# Mosaic-Support.net
KiCad netlist of a schematic drawn in Altium Designer
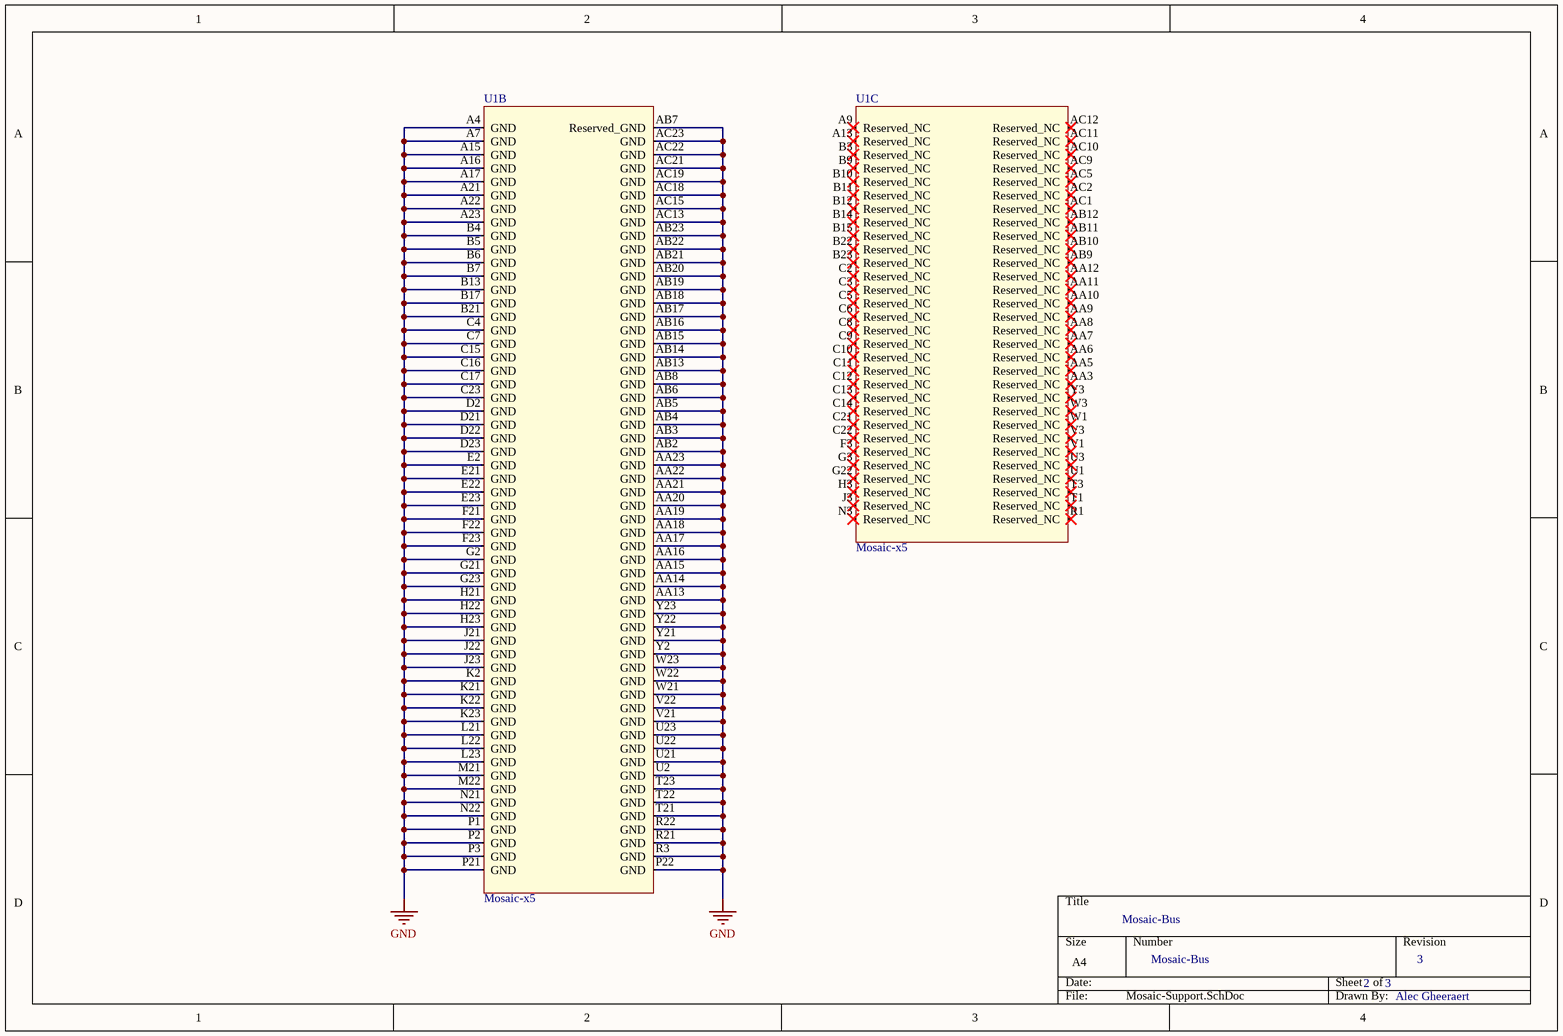
[diagram p0: Mosaic-Support.SchDoc]

(export (version "E")
  (design (tool "Eeschema 10.0.6"))
  (components
    (comp (ref "U1")
      (value "Mosaic-x5")
      (footprint "Mosaic-x5")
      (description "Septentrio Mosaic x5")
      (libsource (lib "Ghrt") (part "Mosaic-x5"))
    )
  )
  (nets
    (net (code "1") (name "GND") (class "Default")
      (node (ref "U1") (pin "A15") (pinfunction "GND_A15") (pintype "power_in"))
      (node (ref "U1") (pin "A16") (pinfunction "GND_A16") (pintype "power_in"))
      (node (ref "U1") (pin "A17") (pinfunction "GND_A17") (pintype "power_in"))
      (node (ref "U1") (pin "A21") (pinfunction "GND_A21") (pintype "power_in"))
      (node (ref "U1") (pin "A22") (pinfunction "GND_A22") (pintype "power_in"))
      (node (ref "U1") (pin "A23") (pinfunction "GND_A23") (pintype "power_in"))
      (node (ref "U1") (pin "A4") (pinfunction "GND_A4") (pintype "power_in"))
      (node (ref "U1") (pin "A7") (pinfunction "GND_A7") (pintype "power_in"))
      (node (ref "U1") (pin "AA13") (pinfunction "GND_AA13") (pintype "power_in"))
      (node (ref "U1") (pin "AA14") (pinfunction "GND_AA14") (pintype "power_in"))
      (node (ref "U1") (pin "AA15") (pinfunction "GND_AA15") (pintype "power_in"))
      (node (ref "U1") (pin "AA16") (pinfunction "GND_AA16") (pintype "power_in"))
      (node (ref "U1") (pin "AA17") (pinfunction "GND_AA17") (pintype "power_in"))
      (node (ref "U1") (pin "AA18") (pinfunction "GND_AA18") (pintype "power_in"))
      (node (ref "U1") (pin "AA19") (pinfunction "GND_AA19") (pintype "power_in"))
      (node (ref "U1") (pin "AA20") (pinfunction "GND_AA20") (pintype "power_in"))
      (node (ref "U1") (pin "AA21") (pinfunction "GND_AA21") (pintype "power_in"))
      (node (ref "U1") (pin "AA22") (pinfunction "GND_AA22") (pintype "power_in"))
      (node (ref "U1") (pin "AA23") (pinfunction "GND_AA23") (pintype "power_in"))
      (node (ref "U1") (pin "AB13") (pinfunction "GND_AB13") (pintype "power_in"))
      (node (ref "U1") (pin "AB14") (pinfunction "GND_AB14") (pintype "power_in"))
      (node (ref "U1") (pin "AB15") (pinfunction "GND_AB15") (pintype "power_in"))
      (node (ref "U1") (pin "AB16") (pinfunction "GND_AB16") (pintype "power_in"))
      (node (ref "U1") (pin "AB17") (pinfunction "GND_AB17") (pintype "power_in"))
      (node (ref "U1") (pin "AB18") (pinfunction "GND_AB18") (pintype "power_in"))
      (node (ref "U1") (pin "AB19") (pinfunction "GND_AB19") (pintype "power_in"))
      (node (ref "U1") (pin "AB2") (pinfunction "GND_AB2") (pintype "power_in"))
      (node (ref "U1") (pin "AB20") (pinfunction "GND_AB20") (pintype "power_in"))
      (node (ref "U1") (pin "AB21") (pinfunction "GND_AB21") (pintype "power_in"))
      (node (ref "U1") (pin "AB22") (pinfunction "GND_AB22") (pintype "power_in"))
      (node (ref "U1") (pin "AB23") (pinfunction "GND_AB23") (pintype "power_in"))
      (node (ref "U1") (pin "AB3") (pinfunction "GND_AB3") (pintype "power_in"))
      (node (ref "U1") (pin "AB4") (pinfunction "GND_AB4") (pintype "power_in"))
      (node (ref "U1") (pin "AB5") (pinfunction "GND_AB5") (pintype "power_in"))
      (node (ref "U1") (pin "AB6") (pinfunction "GND_AB6") (pintype "power_in"))
      (node (ref "U1") (pin "AB7") (pinfunction "Reserved_GND_AB7") (pintype "power_in"))
      (node (ref "U1") (pin "AB8") (pinfunction "GND_AB8") (pintype "power_in"))
      (node (ref "U1") (pin "AC13") (pinfunction "GND_AC13") (pintype "power_in"))
      (node (ref "U1") (pin "AC15") (pinfunction "GND_AC15") (pintype "power_in"))
      (node (ref "U1") (pin "AC18") (pinfunction "GND_AC18") (pintype "power_in"))
      (node (ref "U1") (pin "AC19") (pinfunction "GND_AC19") (pintype "power_in"))
      (node (ref "U1") (pin "AC21") (pinfunction "GND_AC21") (pintype "power_in"))
      (node (ref "U1") (pin "AC22") (pinfunction "GND_AC22") (pintype "power_in"))
      (node (ref "U1") (pin "AC23") (pinfunction "GND_AC23") (pintype "power_in"))
      (node (ref "U1") (pin "B13") (pinfunction "GND_B13") (pintype "power_in"))
      (node (ref "U1") (pin "B17") (pinfunction "GND_B17") (pintype "power_in"))
      (node (ref "U1") (pin "B21") (pinfunction "GND_B21") (pintype "power_in"))
      (node (ref "U1") (pin "B4") (pinfunction "GND_B4") (pintype "power_in"))
      (node (ref "U1") (pin "B5") (pinfunction "GND_B5") (pintype "power_in"))
      (node (ref "U1") (pin "B6") (pinfunction "GND_B6") (pintype "power_in"))
      (node (ref "U1") (pin "B7") (pinfunction "GND_B7") (pintype "power_in"))
      (node (ref "U1") (pin "C15") (pinfunction "GND_C15") (pintype "power_in"))
      (node (ref "U1") (pin "C16") (pinfunction "GND_C16") (pintype "power_in"))
      (node (ref "U1") (pin "C17") (pinfunction "GND_C17") (pintype "power_in"))
      (node (ref "U1") (pin "C23") (pinfunction "GND_C23") (pintype "power_in"))
      (node (ref "U1") (pin "C4") (pinfunction "GND_C4") (pintype "power_in"))
      (node (ref "U1") (pin "C7") (pinfunction "GND_C7") (pintype "power_in"))
      (node (ref "U1") (pin "D2") (pinfunction "GND_D2") (pintype "power_in"))
      (node (ref "U1") (pin "D21") (pinfunction "GND_D21") (pintype "power_in"))
      (node (ref "U1") (pin "D22") (pinfunction "GND_D22") (pintype "power_in"))
      (node (ref "U1") (pin "D23") (pinfunction "GND_D23") (pintype "power_in"))
      (node (ref "U1") (pin "E2") (pinfunction "GND_E2") (pintype "power_in"))
      (node (ref "U1") (pin "E21") (pinfunction "GND_E21") (pintype "power_in"))
      (node (ref "U1") (pin "E22") (pinfunction "GND_E22") (pintype "power_in"))
      (node (ref "U1") (pin "E23") (pinfunction "GND_E23") (pintype "power_in"))
      (node (ref "U1") (pin "F21") (pinfunction "GND_F21") (pintype "power_in"))
      (node (ref "U1") (pin "F22") (pinfunction "GND_F22") (pintype "power_in"))
      (node (ref "U1") (pin "F23") (pinfunction "GND_F23") (pintype "power_in"))
      (node (ref "U1") (pin "G2") (pinfunction "GND_G2") (pintype "power_in"))
      (node (ref "U1") (pin "G21") (pinfunction "GND_G21") (pintype "power_in"))
      (node (ref "U1") (pin "G23") (pinfunction "GND_G23") (pintype "power_in"))
      (node (ref "U1") (pin "H21") (pinfunction "GND_H21") (pintype "power_in"))
      (node (ref "U1") (pin "H22") (pinfunction "GND_H22") (pintype "power_in"))
      (node (ref "U1") (pin "H23") (pinfunction "GND_H23") (pintype "power_in"))
      (node (ref "U1") (pin "J21") (pinfunction "GND_J21") (pintype "power_in"))
      (node (ref "U1") (pin "J22") (pinfunction "GND_J22") (pintype "power_in"))
      (node (ref "U1") (pin "J23") (pinfunction "GND_J23") (pintype "power_in"))
      (node (ref "U1") (pin "K2") (pinfunction "GND_K2") (pintype "power_in"))
      (node (ref "U1") (pin "K21") (pinfunction "GND_K21") (pintype "power_in"))
      (node (ref "U1") (pin "K22") (pinfunction "GND_K22") (pintype "power_in"))
      (node (ref "U1") (pin "K23") (pinfunction "GND_K23") (pintype "power_in"))
      (node (ref "U1") (pin "L21") (pinfunction "GND_L21") (pintype "power_in"))
      (node (ref "U1") (pin "L22") (pinfunction "GND_L22") (pintype "power_in"))
      (node (ref "U1") (pin "L23") (pinfunction "GND_L23") (pintype "power_in"))
      (node (ref "U1") (pin "M21") (pinfunction "GND_M21") (pintype "power_in"))
      (node (ref "U1") (pin "M22") (pinfunction "GND_M22") (pintype "power_in"))
      (node (ref "U1") (pin "N21") (pinfunction "GND_N21") (pintype "power_in"))
      (node (ref "U1") (pin "N22") (pinfunction "GND_N22") (pintype "power_in"))
      (node (ref "U1") (pin "P1") (pinfunction "GND_P1") (pintype "power_in"))
      (node (ref "U1") (pin "P2") (pinfunction "GND_P2") (pintype "power_in"))
      (node (ref "U1") (pin "P21") (pinfunction "GND_P21") (pintype "power_in"))
      (node (ref "U1") (pin "P22") (pinfunction "GND_P22") (pintype "power_in"))
      (node (ref "U1") (pin "P3") (pinfunction "GND_P3") (pintype "power_in"))
      (node (ref "U1") (pin "R21") (pinfunction "GND_R21") (pintype "power_in"))
      (node (ref "U1") (pin "R22") (pinfunction "GND_R22") (pintype "power_in"))
      (node (ref "U1") (pin "R3") (pinfunction "GND_R3") (pintype "power_in"))
      (node (ref "U1") (pin "T21") (pinfunction "GND_T21") (pintype "power_in"))
      (node (ref "U1") (pin "T22") (pinfunction "GND_T22") (pintype "power_in"))
      (node (ref "U1") (pin "T23") (pinfunction "GND_T23") (pintype "power_in"))
      (node (ref "U1") (pin "U2") (pinfunction "GND_U2") (pintype "power_in"))
      (node (ref "U1") (pin "U21") (pinfunction "GND_U21") (pintype "power_in"))
      (node (ref "U1") (pin "U22") (pinfunction "GND_U22") (pintype "power_in"))
      (node (ref "U1") (pin "U23") (pinfunction "GND_U23") (pintype "power_in"))
      (node (ref "U1") (pin "V21") (pinfunction "GND_V21") (pintype "power_in"))
      (node (ref "U1") (pin "V22") (pinfunction "GND_V22") (pintype "power_in"))
      (node (ref "U1") (pin "W21") (pinfunction "GND_W21") (pintype "power_in"))
      (node (ref "U1") (pin "W22") (pinfunction "GND_W22") (pintype "power_in"))
      (node (ref "U1") (pin "W23") (pinfunction "GND_W23") (pintype "power_in"))
      (node (ref "U1") (pin "Y2") (pinfunction "GND_Y2") (pintype "power_in"))
      (node (ref "U1") (pin "Y21") (pinfunction "GND_Y21") (pintype "power_in"))
      (node (ref "U1") (pin "Y22") (pinfunction "GND_Y22") (pintype "power_in"))
      (node (ref "U1") (pin "Y23") (pinfunction "GND_Y23") (pintype "power_in"))
    )
    (net (code "2") (name "unconnected-(U1C-Reserved_NC-PadA9)") (class "Default")
      (node (ref "U1") (pin "A9") (pinfunction "Reserved_NC_A9") (pintype "passive+no_connect"))
    )
    (net (code "3") (name "unconnected-(U1C-Reserved_NC-PadA13)") (class "Default")
      (node (ref "U1") (pin "A13") (pinfunction "Reserved_NC_A13") (pintype "passive+no_connect"))
    )
    (net (code "4") (name "unconnected-(U1C-Reserved_NC-PadAA3)") (class "Default")
      (node (ref "U1") (pin "AA3") (pinfunction "Reserved_NC_AA3") (pintype "passive+no_connect"))
    )
    (net (code "5") (name "unconnected-(U1C-Reserved_NC-PadAA5)") (class "Default")
      (node (ref "U1") (pin "AA5") (pinfunction "Reserved_NC_AA5") (pintype "passive+no_connect"))
    )
    (net (code "6") (name "unconnected-(U1C-Reserved_NC-PadAA6)") (class "Default")
      (node (ref "U1") (pin "AA6") (pinfunction "Reserved_NC_AA6") (pintype "passive+no_connect"))
    )
    (net (code "7") (name "unconnected-(U1C-Reserved_NC-PadAA7)") (class "Default")
      (node (ref "U1") (pin "AA7") (pinfunction "Reserved_NC_AA7") (pintype "passive+no_connect"))
    )
    (net (code "8") (name "unconnected-(U1C-Reserved_NC-PadAA8)") (class "Default")
      (node (ref "U1") (pin "AA8") (pinfunction "Reserved_NC_AA8") (pintype "passive+no_connect"))
    )
    (net (code "9") (name "unconnected-(U1C-Reserved_NC-PadAA9)") (class "Default")
      (node (ref "U1") (pin "AA9") (pinfunction "Reserved_NC_AA9") (pintype "passive+no_connect"))
    )
    (net (code "10") (name "unconnected-(U1C-Reserved_NC-PadAA10)") (class "Default")
      (node (ref "U1") (pin "AA10") (pinfunction "Reserved_NC_AA10") (pintype "passive+no_connect"))
    )
    (net (code "11") (name "unconnected-(U1C-Reserved_NC-PadAA11)") (class "Default")
      (node (ref "U1") (pin "AA11") (pinfunction "Reserved_NC_AA11") (pintype "passive+no_connect"))
    )
    (net (code "12") (name "unconnected-(U1C-Reserved_NC-PadAA12)") (class "Default")
      (node (ref "U1") (pin "AA12") (pinfunction "Reserved_NC_AA12") (pintype "passive+no_connect"))
    )
    (net (code "13") (name "unconnected-(U1C-Reserved_NC-PadAB9)") (class "Default")
      (node (ref "U1") (pin "AB9") (pinfunction "Reserved_NC_AB9") (pintype "passive+no_connect"))
    )
    (net (code "14") (name "unconnected-(U1C-Reserved_NC-PadAB10)") (class "Default")
      (node (ref "U1") (pin "AB10") (pinfunction "Reserved_NC_AB10") (pintype "passive+no_connect"))
    )
    (net (code "15") (name "unconnected-(U1C-Reserved_NC-PadAB11)") (class "Default")
      (node (ref "U1") (pin "AB11") (pinfunction "Reserved_NC_AB11") (pintype "passive+no_connect"))
    )
    (net (code "16") (name "unconnected-(U1C-Reserved_NC-PadAB12)") (class "Default")
      (node (ref "U1") (pin "AB12") (pinfunction "Reserved_NC_AB12") (pintype "passive+no_connect"))
    )
    (net (code "17") (name "unconnected-(U1C-Reserved_NC-PadAC1)") (class "Default")
      (node (ref "U1") (pin "AC1") (pinfunction "Reserved_NC_AC1") (pintype "passive+no_connect"))
    )
    (net (code "18") (name "unconnected-(U1C-Reserved_NC-PadAC2)") (class "Default")
      (node (ref "U1") (pin "AC2") (pinfunction "Reserved_NC_AC2") (pintype "passive+no_connect"))
    )
    (net (code "19") (name "unconnected-(U1C-Reserved_NC-PadAC5)") (class "Default")
      (node (ref "U1") (pin "AC5") (pinfunction "Reserved_NC_AC5") (pintype "passive+no_connect"))
    )
    (net (code "20") (name "unconnected-(U1C-Reserved_NC-PadAC9)") (class "Default")
      (node (ref "U1") (pin "AC9") (pinfunction "Reserved_NC_AC9") (pintype "passive+no_connect"))
    )
    (net (code "21") (name "unconnected-(U1C-Reserved_NC-PadAC10)") (class "Default")
      (node (ref "U1") (pin "AC10") (pinfunction "Reserved_NC_AC10") (pintype "passive+no_connect"))
    )
    (net (code "22") (name "unconnected-(U1C-Reserved_NC-PadAC11)") (class "Default")
      (node (ref "U1") (pin "AC11") (pinfunction "Reserved_NC_AC11") (pintype "passive+no_connect"))
    )
    (net (code "23") (name "unconnected-(U1C-Reserved_NC-PadAC12)") (class "Default")
      (node (ref "U1") (pin "AC12") (pinfunction "Reserved_NC_AC12") (pintype "passive+no_connect"))
    )
    (net (code "24") (name "unconnected-(U1C-Reserved_NC-PadB3)") (class "Default")
      (node (ref "U1") (pin "B3") (pinfunction "Reserved_NC_B3") (pintype "passive+no_connect"))
    )
    (net (code "25") (name "unconnected-(U1C-Reserved_NC-PadB9)") (class "Default")
      (node (ref "U1") (pin "B9") (pinfunction "Reserved_NC_B9") (pintype "passive+no_connect"))
    )
    (net (code "26") (name "unconnected-(U1C-Reserved_NC-PadB10)") (class "Default")
      (node (ref "U1") (pin "B10") (pinfunction "Reserved_NC_B10") (pintype "passive+no_connect"))
    )
    (net (code "27") (name "unconnected-(U1C-Reserved_NC-PadB11)") (class "Default")
      (node (ref "U1") (pin "B11") (pinfunction "Reserved_NC_B11") (pintype "passive+no_connect"))
    )
    (net (code "28") (name "unconnected-(U1C-Reserved_NC-PadB12)") (class "Default")
      (node (ref "U1") (pin "B12") (pinfunction "Reserved_NC_B12") (pintype "passive+no_connect"))
    )
    (net (code "29") (name "unconnected-(U1C-Reserved_NC-PadB14)") (class "Default")
      (node (ref "U1") (pin "B14") (pinfunction "Reserved_NC_B14") (pintype "passive+no_connect"))
    )
    (net (code "30") (name "unconnected-(U1C-Reserved_NC-PadB15)") (class "Default")
      (node (ref "U1") (pin "B15") (pinfunction "Reserved_NC_B15") (pintype "passive+no_connect"))
    )
    (net (code "31") (name "unconnected-(U1C-Reserved_NC-PadB22)") (class "Default")
      (node (ref "U1") (pin "B22") (pinfunction "Reserved_NC_B22") (pintype "passive+no_connect"))
    )
    (net (code "32") (name "unconnected-(U1C-Reserved_NC-PadB23)") (class "Default")
      (node (ref "U1") (pin "B23") (pinfunction "Reserved_NC_B23") (pintype "passive+no_connect"))
    )
    (net (code "33") (name "unconnected-(U1C-Reserved_NC-PadC2)") (class "Default")
      (node (ref "U1") (pin "C2") (pinfunction "Reserved_NC_C2") (pintype "passive+no_connect"))
    )
    (net (code "34") (name "unconnected-(U1C-Reserved_NC-PadC3)") (class "Default")
      (node (ref "U1") (pin "C3") (pinfunction "Reserved_NC_C3") (pintype "passive+no_connect"))
    )
    (net (code "35") (name "unconnected-(U1C-Reserved_NC-PadC5)") (class "Default")
      (node (ref "U1") (pin "C5") (pinfunction "Reserved_NC_C5") (pintype "passive+no_connect"))
    )
    (net (code "36") (name "unconnected-(U1C-Reserved_NC-PadC6)") (class "Default")
      (node (ref "U1") (pin "C6") (pinfunction "Reserved_NC_C6") (pintype "passive+no_connect"))
    )
    (net (code "37") (name "unconnected-(U1C-Reserved_NC-PadC8)") (class "Default")
      (node (ref "U1") (pin "C8") (pinfunction "Reserved_NC_C8") (pintype "passive+no_connect"))
    )
    (net (code "38") (name "unconnected-(U1C-Reserved_NC-PadC9)") (class "Default")
      (node (ref "U1") (pin "C9") (pinfunction "Reserved_NC_C9") (pintype "passive+no_connect"))
    )
    (net (code "39") (name "unconnected-(U1C-Reserved_NC-PadC10)") (class "Default")
      (node (ref "U1") (pin "C10") (pinfunction "Reserved_NC_C10") (pintype "passive+no_connect"))
    )
    (net (code "40") (name "unconnected-(U1C-Reserved_NC-PadC11)") (class "Default")
      (node (ref "U1") (pin "C11") (pinfunction "Reserved_NC_C11") (pintype "passive+no_connect"))
    )
    (net (code "41") (name "unconnected-(U1C-Reserved_NC-PadC12)") (class "Default")
      (node (ref "U1") (pin "C12") (pinfunction "Reserved_NC_C12") (pintype "passive+no_connect"))
    )
    (net (code "42") (name "unconnected-(U1C-Reserved_NC-PadC13)") (class "Default")
      (node (ref "U1") (pin "C13") (pinfunction "Reserved_NC_C13") (pintype "passive+no_connect"))
    )
    (net (code "43") (name "unconnected-(U1C-Reserved_NC-PadC14)") (class "Default")
      (node (ref "U1") (pin "C14") (pinfunction "Reserved_NC_C14") (pintype "passive+no_connect"))
    )
    (net (code "44") (name "unconnected-(U1C-Reserved_NC-PadC21)") (class "Default")
      (node (ref "U1") (pin "C21") (pinfunction "Reserved_NC_C21") (pintype "passive+no_connect"))
    )
    (net (code "45") (name "unconnected-(U1C-Reserved_NC-PadC22)") (class "Default")
      (node (ref "U1") (pin "C22") (pinfunction "Reserved_NC_C22") (pintype "passive+no_connect"))
    )
    (net (code "46") (name "unconnected-(U1C-Reserved_NC-PadF3)") (class "Default")
      (node (ref "U1") (pin "F3") (pinfunction "Reserved_NC_F3") (pintype "passive+no_connect"))
    )
    (net (code "47") (name "unconnected-(U1C-Reserved_NC-PadG3)") (class "Default")
      (node (ref "U1") (pin "G3") (pinfunction "Reserved_NC_G3") (pintype "passive+no_connect"))
    )
    (net (code "48") (name "unconnected-(U1C-Reserved_NC-PadG22)") (class "Default")
      (node (ref "U1") (pin "G22") (pinfunction "Reserved_NC_G22") (pintype "passive+no_connect"))
    )
    (net (code "49") (name "unconnected-(U1C-Reserved_NC-PadH3)") (class "Default")
      (node (ref "U1") (pin "H3") (pinfunction "Reserved_NC_H3") (pintype "passive+no_connect"))
    )
    (net (code "50") (name "unconnected-(U1C-Reserved_NC-PadJ3)") (class "Default")
      (node (ref "U1") (pin "J3") (pinfunction "Reserved_NC_J3") (pintype "passive+no_connect"))
    )
    (net (code "51") (name "unconnected-(U1C-Reserved_NC-PadN3)") (class "Default")
      (node (ref "U1") (pin "N3") (pinfunction "Reserved_NC_N3") (pintype "passive+no_connect"))
    )
    (net (code "52") (name "unconnected-(U1C-Reserved_NC-PadR1)") (class "Default")
      (node (ref "U1") (pin "R1") (pinfunction "Reserved_NC_R1") (pintype "passive+no_connect"))
    )
    (net (code "53") (name "unconnected-(U1C-Reserved_NC-PadT1)") (class "Default")
      (node (ref "U1") (pin "T1") (pinfunction "Reserved_NC_T1") (pintype "passive+no_connect"))
    )
    (net (code "54") (name "unconnected-(U1C-Reserved_NC-PadT3)") (class "Default")
      (node (ref "U1") (pin "T3") (pinfunction "Reserved_NC_T3") (pintype "passive+no_connect"))
    )
    (net (code "55") (name "unconnected-(U1C-Reserved_NC-PadU1)") (class "Default")
      (node (ref "U1") (pin "U1") (pinfunction "Reserved_NC_U1") (pintype "passive+no_connect"))
    )
    (net (code "56") (name "unconnected-(U1C-Reserved_NC-PadU3)") (class "Default")
      (node (ref "U1") (pin "U3") (pinfunction "Reserved_NC_U3") (pintype "passive+no_connect"))
    )
    (net (code "57") (name "unconnected-(U1C-Reserved_NC-PadV1)") (class "Default")
      (node (ref "U1") (pin "V1") (pinfunction "Reserved_NC_V1") (pintype "passive+no_connect"))
    )
    (net (code "58") (name "unconnected-(U1C-Reserved_NC-PadV3)") (class "Default")
      (node (ref "U1") (pin "V3") (pinfunction "Reserved_NC_V3") (pintype "passive+no_connect"))
    )
    (net (code "59") (name "unconnected-(U1C-Reserved_NC-PadW1)") (class "Default")
      (node (ref "U1") (pin "W1") (pinfunction "Reserved_NC_W1") (pintype "passive+no_connect"))
    )
    (net (code "60") (name "unconnected-(U1C-Reserved_NC-PadW3)") (class "Default")
      (node (ref "U1") (pin "W3") (pinfunction "Reserved_NC_W3") (pintype "passive+no_connect"))
    )
    (net (code "61") (name "unconnected-(U1C-Reserved_NC-PadY3)") (class "Default")
      (node (ref "U1") (pin "Y3") (pinfunction "Reserved_NC_Y3") (pintype "passive+no_connect"))
    )
  )
)
